# Sheet1.net
KiCad netlist of a schematic drawn in Altium Designer
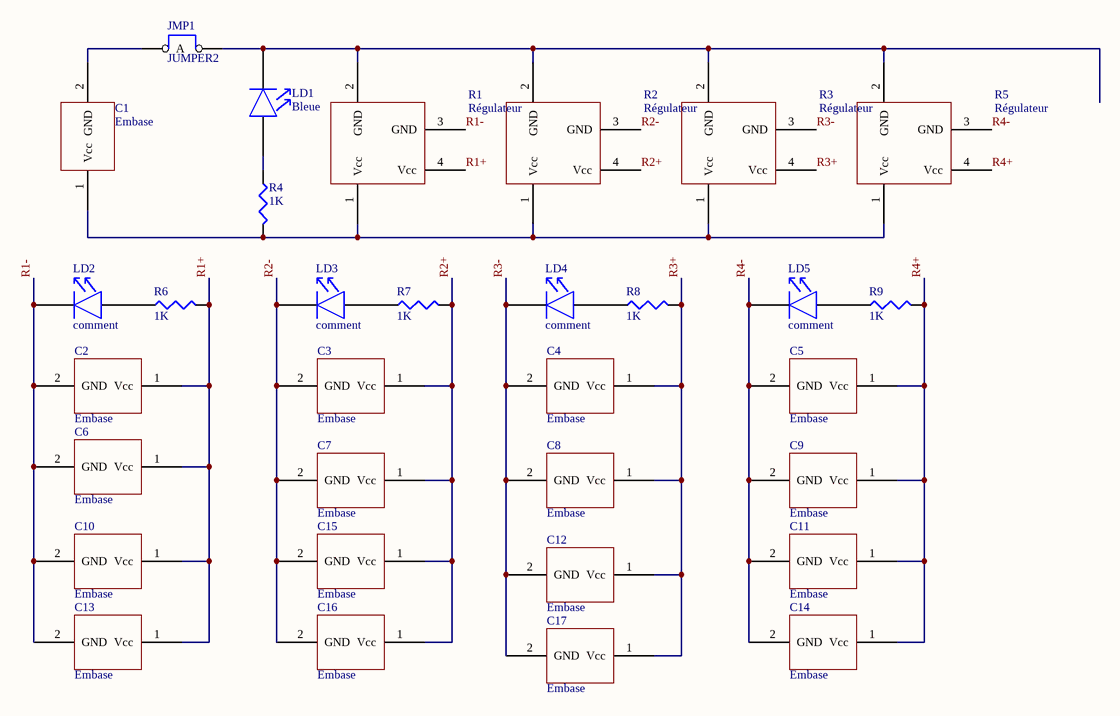
[diagram p0: Sheet1.SchDoc]

(export (version "E")
  (design (tool "Eeschema 10.0.6"))
  (components
    (comp (ref "C1")
      (value "Embase")
      (footprint "POWER__2")
      (description "Embase 2 broches")
      (libsource (lib "") (part "Embase_1"))
    )
    (comp (ref "C2")
      (value "Embase")
      (footprint "POWER__2")
      (description "Embase 2 broches")
      (libsource (lib "Schlib1") (part "Embase"))
    )
    (comp (ref "C3")
      (value "Embase")
      (footprint "POWER__2")
      (description "Embase 2 broches")
      (libsource (lib "Schlib1") (part "Embase"))
    )
    (comp (ref "C4")
      (value "Embase")
      (footprint "POWER__2")
      (description "Embase 2 broches")
      (libsource (lib "Schlib1") (part "Embase"))
    )
    (comp (ref "C5")
      (value "Embase")
      (footprint "POWER__2")
      (description "Embase 2 broches")
      (libsource (lib "Schlib1") (part "Embase"))
    )
    (comp (ref "C6")
      (value "Embase")
      (footprint "POWER__2")
      (description "Embase 2 broches")
      (libsource (lib "Schlib1") (part "Embase"))
    )
    (comp (ref "C7")
      (value "Embase")
      (footprint "POWER__2")
      (description "Embase 2 broches")
      (libsource (lib "Schlib1") (part "Embase"))
    )
    (comp (ref "C8")
      (value "Embase")
      (footprint "POWER__2")
      (description "Embase 2 broches")
      (libsource (lib "Schlib1") (part "Embase"))
    )
    (comp (ref "C9")
      (value "Embase")
      (footprint "POWER__2")
      (description "Embase 2 broches")
      (libsource (lib "Schlib1") (part "Embase"))
    )
    (comp (ref "C10")
      (value "Embase")
      (footprint "POWER__2")
      (description "Embase 2 broches")
      (libsource (lib "Schlib1") (part "Embase"))
    )
    (comp (ref "C11")
      (value "Embase")
      (footprint "POWER__2")
      (description "Embase 2 broches")
      (libsource (lib "Schlib1") (part "Embase"))
    )
    (comp (ref "C12")
      (value "Embase")
      (footprint "POWER__2")
      (description "Embase 2 broches")
      (libsource (lib "Schlib1") (part "Embase"))
    )
    (comp (ref "C13")
      (value "Embase")
      (footprint "POWER__2")
      (description "Embase 2 broches")
      (libsource (lib "Schlib1") (part "Embase"))
    )
    (comp (ref "C14")
      (value "Embase")
      (footprint "POWER__2")
      (description "Embase 2 broches")
      (libsource (lib "Schlib1") (part "Embase"))
    )
    (comp (ref "C15")
      (value "Embase")
      (footprint "POWER__2")
      (description "Embase 2 broches")
      (libsource (lib "Schlib1") (part "Embase"))
    )
    (comp (ref "C16")
      (value "Embase")
      (footprint "POWER__2")
      (description "Embase 2 broches")
      (libsource (lib "Schlib1") (part "Embase"))
    )
    (comp (ref "C17")
      (value "Embase")
      (footprint "POWER__2")
      (description "Embase 2 broches")
      (libsource (lib "Schlib1") (part "Embase"))
    )
    (comp (ref "JMP1")
      (value "JUMPER2")
      (footprint "JMP2-100")
      (description "cavalier 1 position")
      (libsource (lib "ISEN_basics") (part "JUMPER2"))
    )
    (comp (ref "LD1")
      (value "Bleue")
      (footprint "LED1206")
      (description "LED 5mm/3mm/CMS")
      (libsource (lib "ISEN_basics") (part "LED"))
    )
    (comp (ref "LD2")
      (value "comment")
      (footprint "LED1206")
      (description "LED 5mm/3mm/CMS")
      (libsource (lib "ISEN_basics") (part "LED"))
    )
    (comp (ref "LD3")
      (value "comment")
      (footprint "LED1206")
      (description "LED 5mm/3mm/CMS")
      (libsource (lib "ISEN_basics") (part "LED"))
    )
    (comp (ref "LD4")
      (value "comment")
      (footprint "LED1206")
      (description "LED 5mm/3mm/CMS")
      (libsource (lib "ISEN_basics") (part "LED"))
    )
    (comp (ref "LD5")
      (value "comment")
      (footprint "LED1206")
      (description "LED 5mm/3mm/CMS")
      (libsource (lib "ISEN_basics") (part "LED"))
    )
    (comp (ref "R1")
      (value "Régulateur")
      (footprint "Régulateur")
      (description "Régulateur de tension")
      (libsource (lib "Schlib1") (part "Régulateur"))
    )
    (comp (ref "R2")
      (value "Régulateur")
      (footprint "Régulateur")
      (description "Régulateur de tension")
      (libsource (lib "Schlib1") (part "Régulateur"))
    )
    (comp (ref "R3")
      (value "Régulateur")
      (footprint "Régulateur")
      (description "Régulateur de tension")
      (libsource (lib "Schlib1") (part "Régulateur"))
    )
    (comp (ref "R4")
      (value "1K")
      (footprint "0805")
      (description "resistance")
      (libsource (lib "ISEN_basics") (part "RES"))
    )
    (comp (ref "R5")
      (value "Régulateur")
      (footprint "Régulateur")
      (description "Régulateur de tension")
      (libsource (lib "Schlib1") (part "Régulateur"))
    )
    (comp (ref "R6")
      (value "1K")
      (footprint "0805")
      (description "resistance")
      (fields (field (name "Comment") "RES"))
      (libsource (lib "ISEN_basics") (part "RES"))
    )
    (comp (ref "R7")
      (value "1K")
      (footprint "0805")
      (description "resistance")
      (fields (field (name "Comment") "RES"))
      (libsource (lib "ISEN_basics") (part "RES"))
    )
    (comp (ref "R8")
      (value "1K")
      (footprint "0805")
      (description "resistance")
      (fields (field (name "Comment") "RES"))
      (libsource (lib "ISEN_basics") (part "RES"))
    )
    (comp (ref "R9")
      (value "1K")
      (footprint "0805")
      (description "resistance")
      (fields (field (name "Comment") "RES"))
      (libsource (lib "ISEN_basics") (part "RES"))
    )
  )
  (nets
    (net (code "1") (name "/R1+") (class "Default")
      (node (ref "C10") (pin "1") (pinfunction "Vcc_1") (pintype "power_in"))
      (node (ref "C13") (pin "1") (pinfunction "Vcc_1") (pintype "power_in"))
      (node (ref "C2") (pin "1") (pinfunction "Vcc_1") (pintype "power_in"))
      (node (ref "C6") (pin "1") (pinfunction "Vcc_1") (pintype "power_in"))
      (node (ref "R1") (pin "4") (pinfunction "Vcc_4") (pintype "power_in"))
      (node (ref "R6") (pin "2") (pintype "passive"))
    )
    (net (code "2") (name "/R1-") (class "Default")
      (node (ref "C10") (pin "2") (pinfunction "GND_2") (pintype "power_in"))
      (node (ref "C13") (pin "2") (pinfunction "GND_2") (pintype "power_in"))
      (node (ref "C2") (pin "2") (pinfunction "GND_2") (pintype "power_in"))
      (node (ref "C6") (pin "2") (pinfunction "GND_2") (pintype "power_in"))
      (node (ref "LD2") (pin "K") (pinfunction "10_K") (pintype "passive"))
      (node (ref "R1") (pin "3") (pinfunction "GND_3") (pintype "power_in"))
    )
    (net (code "3") (name "/R2+") (class "Default")
      (node (ref "C15") (pin "1") (pinfunction "Vcc_1") (pintype "power_in"))
      (node (ref "C16") (pin "1") (pinfunction "Vcc_1") (pintype "power_in"))
      (node (ref "C3") (pin "1") (pinfunction "Vcc_1") (pintype "power_in"))
      (node (ref "C7") (pin "1") (pinfunction "Vcc_1") (pintype "power_in"))
      (node (ref "R2") (pin "4") (pinfunction "Vcc_4") (pintype "power_in"))
      (node (ref "R7") (pin "2") (pintype "passive"))
    )
    (net (code "4") (name "/R2-") (class "Default")
      (node (ref "C15") (pin "2") (pinfunction "GND_2") (pintype "power_in"))
      (node (ref "C16") (pin "2") (pinfunction "GND_2") (pintype "power_in"))
      (node (ref "C3") (pin "2") (pinfunction "GND_2") (pintype "power_in"))
      (node (ref "C7") (pin "2") (pinfunction "GND_2") (pintype "power_in"))
      (node (ref "LD3") (pin "K") (pinfunction "10_K") (pintype "passive"))
      (node (ref "R2") (pin "3") (pinfunction "GND_3") (pintype "power_in"))
    )
    (net (code "5") (name "/R3+") (class "Default")
      (node (ref "C12") (pin "1") (pinfunction "Vcc_1") (pintype "power_in"))
      (node (ref "C17") (pin "1") (pinfunction "Vcc_1") (pintype "power_in"))
      (node (ref "C4") (pin "1") (pinfunction "Vcc_1") (pintype "power_in"))
      (node (ref "C8") (pin "1") (pinfunction "Vcc_1") (pintype "power_in"))
      (node (ref "R3") (pin "4") (pinfunction "Vcc_4") (pintype "power_in"))
      (node (ref "R8") (pin "2") (pintype "passive"))
    )
    (net (code "6") (name "/R3-") (class "Default")
      (node (ref "C12") (pin "2") (pinfunction "GND_2") (pintype "power_in"))
      (node (ref "C17") (pin "2") (pinfunction "GND_2") (pintype "power_in"))
      (node (ref "C4") (pin "2") (pinfunction "GND_2") (pintype "power_in"))
      (node (ref "C8") (pin "2") (pinfunction "GND_2") (pintype "power_in"))
      (node (ref "LD4") (pin "K") (pinfunction "10_K") (pintype "passive"))
      (node (ref "R3") (pin "3") (pinfunction "GND_3") (pintype "power_in"))
    )
    (net (code "7") (name "/R4+") (class "Default")
      (node (ref "C11") (pin "1") (pinfunction "Vcc_1") (pintype "power_in"))
      (node (ref "C14") (pin "1") (pinfunction "Vcc_1") (pintype "power_in"))
      (node (ref "C5") (pin "1") (pinfunction "Vcc_1") (pintype "power_in"))
      (node (ref "C9") (pin "1") (pinfunction "Vcc_1") (pintype "power_in"))
      (node (ref "R5") (pin "4") (pinfunction "Vcc_4") (pintype "power_in"))
      (node (ref "R9") (pin "2") (pintype "passive"))
    )
    (net (code "8") (name "/R4-") (class "Default")
      (node (ref "C11") (pin "2") (pinfunction "GND_2") (pintype "power_in"))
      (node (ref "C14") (pin "2") (pinfunction "GND_2") (pintype "power_in"))
      (node (ref "C5") (pin "2") (pinfunction "GND_2") (pintype "power_in"))
      (node (ref "C9") (pin "2") (pinfunction "GND_2") (pintype "power_in"))
      (node (ref "LD5") (pin "K") (pinfunction "10_K") (pintype "passive"))
      (node (ref "R5") (pin "3") (pinfunction "GND_3") (pintype "power_in"))
    )
    (net (code "9") (name "Net-(C1-GND)") (class "Default")
      (node (ref "C1") (pin "2") (pinfunction "GND_2") (pintype "power_in"))
      (node (ref "JMP1") (pin "1") (pinfunction "A_1") (pintype "passive"))
    )
    (net (code "10") (name "Net-(C1-Vcc)") (class "Default")
      (node (ref "C1") (pin "1") (pinfunction "Vcc_1") (pintype "power_in"))
      (node (ref "R1") (pin "1") (pinfunction "Vcc_1") (pintype "open_emitter"))
      (node (ref "R2") (pin "1") (pinfunction "Vcc_1") (pintype "open_emitter"))
      (node (ref "R3") (pin "1") (pinfunction "Vcc_1") (pintype "open_emitter"))
      (node (ref "R4") (pin "2") (pintype "passive"))
      (node (ref "R5") (pin "1") (pinfunction "Vcc_1") (pintype "open_emitter"))
    )
    (net (code "11") (name "Net-(JMP1-com)") (class "Default")
      (node (ref "JMP1") (pin "2") (pinfunction "com_2") (pintype "passive"))
      (node (ref "LD1") (pin "K") (pinfunction "10_K") (pintype "passive"))
      (node (ref "R1") (pin "2") (pinfunction "GND_2") (pintype "power_in"))
      (node (ref "R2") (pin "2") (pinfunction "GND_2") (pintype "power_in"))
      (node (ref "R3") (pin "2") (pinfunction "GND_2") (pintype "power_in"))
      (node (ref "R5") (pin "2") (pinfunction "GND_2") (pintype "power_in"))
    )
    (net (code "12") (name "Net-(LD1-8)") (class "Default")
      (node (ref "LD1") (pin "A") (pinfunction "8_A") (pintype "passive"))
      (node (ref "R4") (pin "1") (pintype "passive"))
    )
    (net (code "13") (name "Net-(LD2-8)") (class "Default")
      (node (ref "LD2") (pin "A") (pinfunction "8_A") (pintype "passive"))
      (node (ref "R6") (pin "1") (pintype "passive"))
    )
    (net (code "14") (name "Net-(LD3-8)") (class "Default")
      (node (ref "LD3") (pin "A") (pinfunction "8_A") (pintype "passive"))
      (node (ref "R7") (pin "1") (pintype "passive"))
    )
    (net (code "15") (name "Net-(LD4-8)") (class "Default")
      (node (ref "LD4") (pin "A") (pinfunction "8_A") (pintype "passive"))
      (node (ref "R8") (pin "1") (pintype "passive"))
    )
    (net (code "16") (name "Net-(LD5-8)") (class "Default")
      (node (ref "LD5") (pin "A") (pinfunction "8_A") (pintype "passive"))
      (node (ref "R9") (pin "1") (pintype "passive"))
    )
  )
)
